# uDuino.net
KiCad netlist of a schematic drawn in EAGLE
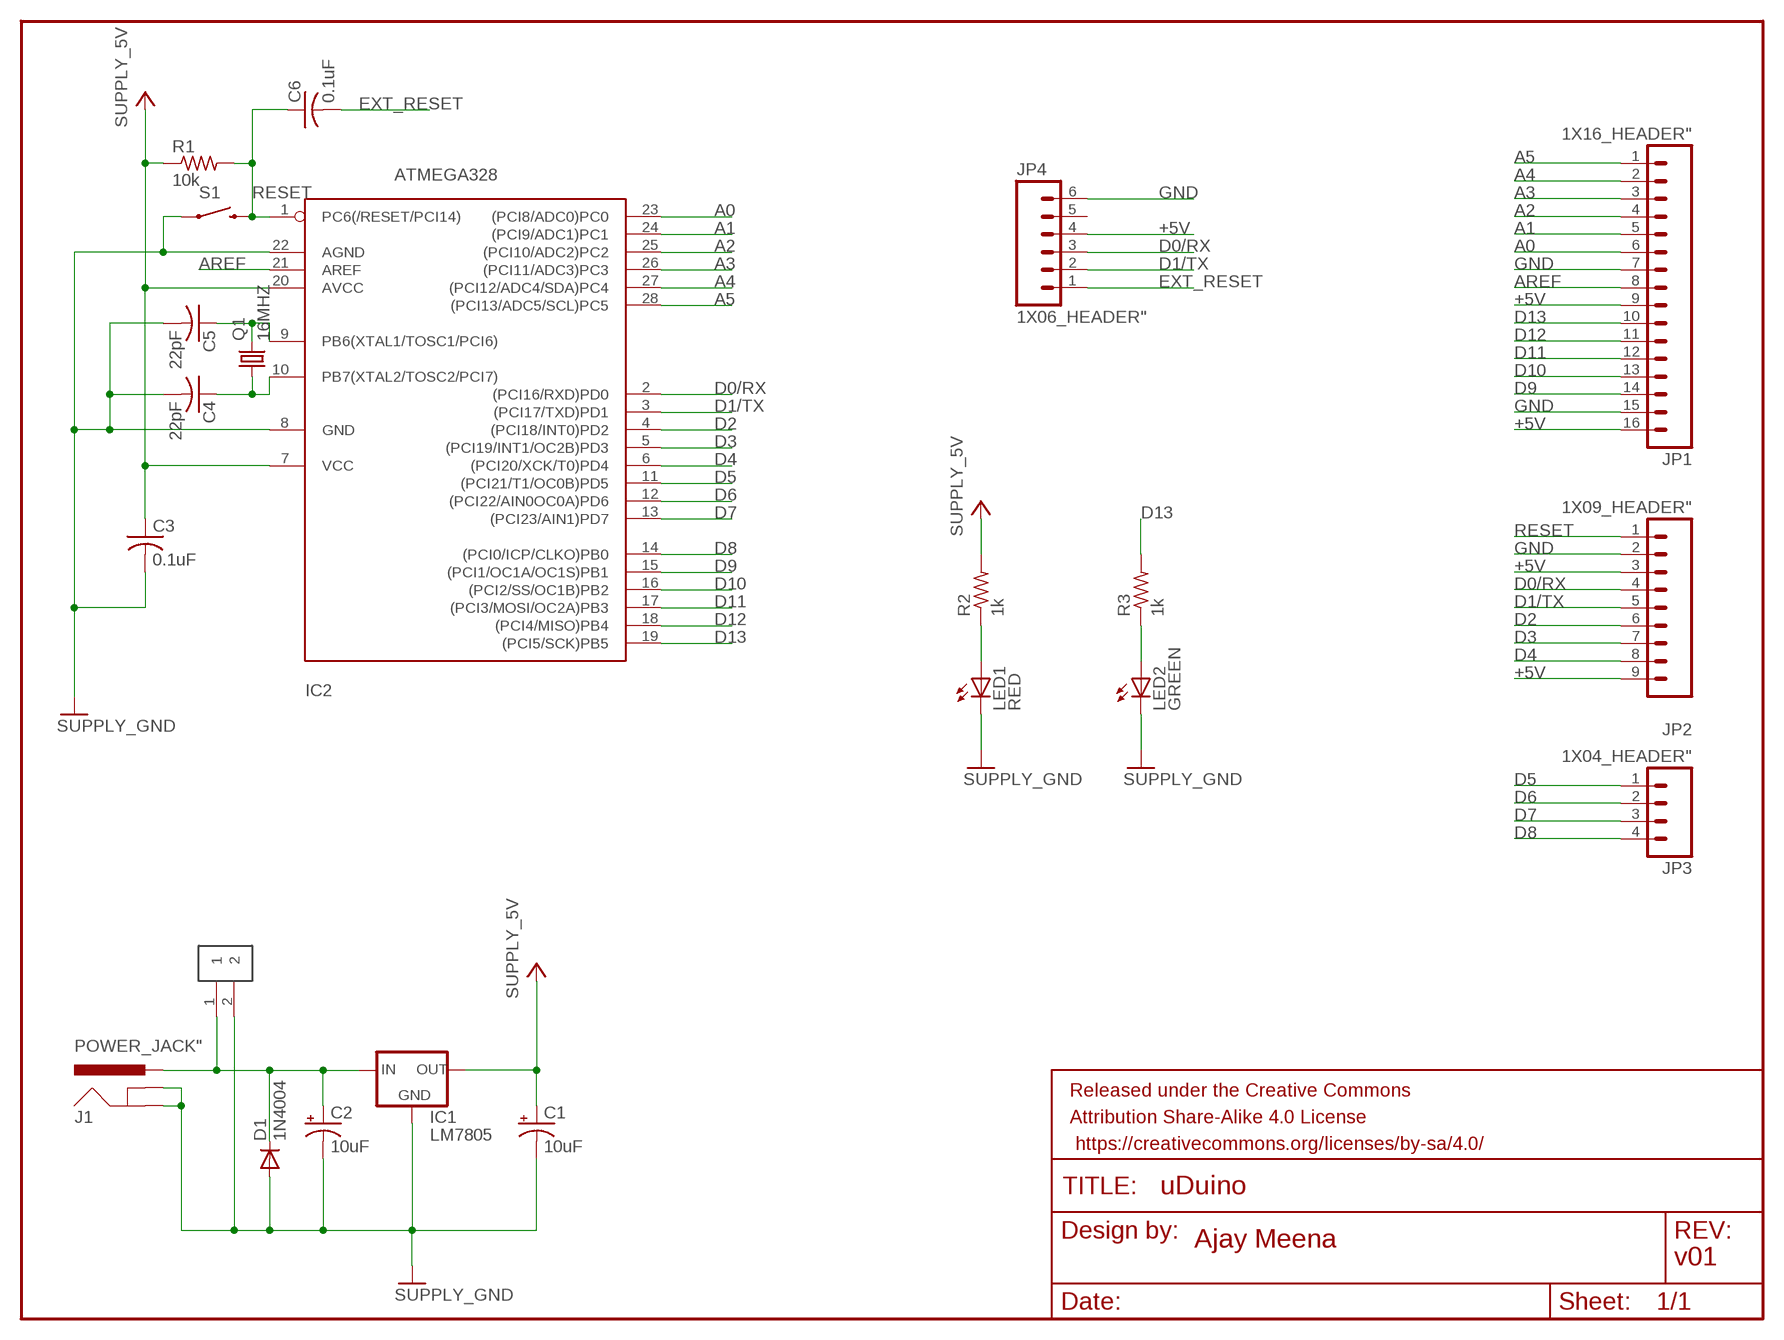
[diagram p0: schematic, sheet 1]

(export (version "E")
  (design (tool "Eeschema 10.0.6"))
  (components
    (comp (ref "C1")
      (value "10uF")
      (footprint "eagle-import:ELECTROLYTIC_CAP")
      (libsource (lib "eagle-import") (part "ELECTROLYTIC_CAP2.54MM"))
    )
    (comp (ref "C2")
      (value "10uF")
      (footprint "eagle-import:ELECTROLYTIC_CAP")
      (libsource (lib "eagle-import") (part "ELECTROLYTIC_CAP2.54MM"))
    )
    (comp (ref "C3")
      (value "0.1uF")
      (footprint "eagle-import:UNPOLARIZED_CAP")
      (libsource (lib "eagle-import") (part "UNPOLARIZED_CAP{dblquote}"))
    )
    (comp (ref "C4")
      (value "22pF")
      (footprint "eagle-import:UNPOLARIZED_CAP")
      (libsource (lib "eagle-import") (part "UNPOLARIZED_CAP{dblquote}"))
    )
    (comp (ref "C5")
      (value "22pF")
      (footprint "eagle-import:UNPOLARIZED_CAP")
      (libsource (lib "eagle-import") (part "UNPOLARIZED_CAP{dblquote}"))
    )
    (comp (ref "C6")
      (value "0.1uF")
      (footprint "eagle-import:UNPOLARIZED_CAP")
      (libsource (lib "eagle-import") (part "UNPOLARIZED_CAP{dblquote}"))
    )
    (comp (ref "D1")
      (value "1N4004")
      (footprint "eagle-import:DO41-10")
      (libsource (lib "eagle-import") (part "1N4004"))
    )
    (comp (ref "FRAME1")
      (value "FRAME-LETTERNO_PACKAGE")
      (footprint "eagle-import:DUMMY")
      (fields
        (field (name "DESIGNER") "Nobody")
        (field (name "VERSION") "v01")
        (field (name "DESIGNER_1") "Ajay Meena")
      )
      (libsource (lib "eagle-import") (part "FRAME-LETTERNO_PACKAGE"))
    )
    (comp (ref "IC1")
      (value "LM7805")
      (footprint "eagle-import:L4931_REGULATOR")
      (libsource (lib "eagle-import") (part "REGULATOR"))
    )
    (comp (ref "IC2")
      (value "ATMEGA328")
      (footprint "eagle-import:ATMEGA328")
      (libsource (lib "eagle-import") (part "ATMEGA328{dblquote}"))
    )
    (comp (ref "J1")
      (value "POWER_JACK\"")
      (footprint "eagle-import:POWER_JACK")
      (libsource (lib "eagle-import") (part "POWER_JACK{dblquote}"))
    )
    (comp (ref "JP1")
      (value "1X16_HEADER\"")
      (footprint "eagle-import:1X16_HEADER")
      (libsource (lib "eagle-import") (part "1X16_HEADER{dblquote}"))
    )
    (comp (ref "JP2")
      (value "1X09_HEADER\"")
      (footprint "eagle-import:1X09_HEADER")
      (libsource (lib "eagle-import") (part "1X09_HEADER{dblquote}"))
    )
    (comp (ref "JP3")
      (value "1X04_HEADER\"")
      (footprint "eagle-import:1X04_HEADER")
      (libsource (lib "eagle-import") (part "1X04_HEADER{dblquote}"))
    )
    (comp (ref "JP4")
      (value "1X06_HEADER\"")
      (footprint "eagle-import:1X06_HEADER")
      (libsource (lib "eagle-import") (part "1X06_HEADER{dblquote}"))
    )
    (comp (ref "LED1")
      (value "RED")
      (footprint "eagle-import:LED5MM")
      (libsource (lib "eagle-import") (part "LED5MM"))
    )
    (comp (ref "LED2")
      (value "GREEN")
      (footprint "eagle-import:LED5MM")
      (libsource (lib "eagle-import") (part "LED5MM"))
    )
    (comp (ref "Q1")
      (value "16MHZ")
      (footprint "eagle-import:HC49_S")
      (libsource (lib "eagle-import") (part "CRYSTALHC49S"))
    )
    (comp (ref "R1")
      (value "10k")
      (footprint "eagle-import:0204_7")
      (libsource (lib "eagle-import") (part "R-US_0204/7"))
    )
    (comp (ref "R2")
      (value "1k")
      (footprint "eagle-import:0204_7")
      (libsource (lib "eagle-import") (part "R-US_0204/7"))
    )
    (comp (ref "R3")
      (value "1k")
      (footprint "eagle-import:0204_7")
      (libsource (lib "eagle-import") (part "R-US_0204/7"))
    )
    (comp (ref "S1")
      (value "MOMENTARY_SWITCH\"")
      (footprint "eagle-import:MOMENTARY_SWITCH")
      (libsource (lib "eagle-import") (part "MOMENTARY_SWITCH{dblquote}"))
    )
    (comp (ref "U$1")
      (value "1X02_HEADER")
      (footprint "eagle-import:1X02_HEADER")
      (libsource (lib "eagle-import") (part "1X02_HEADER"))
    )
  )
  (nets
    (net (code "1") (name "/A0") (class "Default")
      (node (ref "IC2") (pin "23") (pinfunction "(PCI8/ADC0)PC0_23") (pintype "bidirectional"))
      (node (ref "JP1") (pin "6") (pinfunction "6_6") (pintype "passive"))
    )
    (net (code "2") (name "/A1") (class "Default")
      (node (ref "IC2") (pin "24") (pinfunction "(PCI9/ADC1)PC1_24") (pintype "bidirectional"))
      (node (ref "JP1") (pin "5") (pinfunction "5_5") (pintype "passive"))
    )
    (net (code "3") (name "/A2") (class "Default")
      (node (ref "IC2") (pin "25") (pinfunction "(PCI10/ADC2)PC2_25") (pintype "bidirectional"))
      (node (ref "JP1") (pin "4") (pinfunction "4_4") (pintype "passive"))
    )
    (net (code "4") (name "/A3") (class "Default")
      (node (ref "IC2") (pin "26") (pinfunction "(PCI11/ADC3)PC3_26") (pintype "bidirectional"))
      (node (ref "JP1") (pin "3") (pinfunction "3_3") (pintype "passive"))
    )
    (net (code "5") (name "/A4") (class "Default")
      (node (ref "IC2") (pin "27") (pinfunction "(PCI12/ADC4/SDA)PC4_27") (pintype "bidirectional"))
      (node (ref "JP1") (pin "2") (pinfunction "2_2") (pintype "passive"))
    )
    (net (code "6") (name "/A5") (class "Default")
      (node (ref "IC2") (pin "28") (pinfunction "(PCI13/ADC5/SCL)PC5_28") (pintype "bidirectional"))
      (node (ref "JP1") (pin "1") (pinfunction "1_1") (pintype "passive"))
    )
    (net (code "7") (name "/AREF") (class "Default")
      (node (ref "IC2") (pin "21") (pinfunction "AREF_21") (pintype "bidirectional"))
      (node (ref "JP1") (pin "8") (pinfunction "8_8") (pintype "passive"))
    )
    (net (code "8") (name "/D0{slash}RX") (class "Default")
      (node (ref "IC2") (pin "2") (pinfunction "(PCI16/RXD)PD0_2") (pintype "bidirectional"))
      (node (ref "JP2") (pin "4") (pinfunction "4_4") (pintype "passive"))
      (node (ref "JP4") (pin "3") (pinfunction "3_3") (pintype "passive"))
    )
    (net (code "9") (name "/D1{slash}TX") (class "Default")
      (node (ref "IC2") (pin "3") (pinfunction "(PCI17/TXD)PD1_3") (pintype "bidirectional"))
      (node (ref "JP2") (pin "5") (pinfunction "5_5") (pintype "passive"))
      (node (ref "JP4") (pin "2") (pinfunction "2_2") (pintype "passive"))
    )
    (net (code "10") (name "/D2") (class "Default")
      (node (ref "IC2") (pin "4") (pinfunction "(PCI18/INT0)PD2_4") (pintype "bidirectional"))
      (node (ref "JP2") (pin "6") (pinfunction "6_6") (pintype "passive"))
    )
    (net (code "11") (name "/D3") (class "Default")
      (node (ref "IC2") (pin "5") (pinfunction "(PCI19/INT1/OC2B)PD3_5") (pintype "bidirectional"))
      (node (ref "JP2") (pin "7") (pinfunction "7_7") (pintype "passive"))
    )
    (net (code "12") (name "/D4") (class "Default")
      (node (ref "IC2") (pin "6") (pinfunction "(PCI20/XCK/T0)PD4_6") (pintype "bidirectional"))
      (node (ref "JP2") (pin "8") (pinfunction "8_8") (pintype "passive"))
    )
    (net (code "13") (name "/D5") (class "Default")
      (node (ref "IC2") (pin "11") (pinfunction "(PCI21/T1/OC0B)PD5_11") (pintype "bidirectional"))
      (node (ref "JP3") (pin "1") (pinfunction "1_1") (pintype "passive"))
    )
    (net (code "14") (name "/D6") (class "Default")
      (node (ref "IC2") (pin "12") (pinfunction "(PCI22/AIN0OC0A)PD6_12") (pintype "bidirectional"))
      (node (ref "JP3") (pin "2") (pinfunction "2_2") (pintype "passive"))
    )
    (net (code "15") (name "/D7") (class "Default")
      (node (ref "IC2") (pin "13") (pinfunction "(PCI23/AIN1)PD7_13") (pintype "bidirectional"))
      (node (ref "JP3") (pin "3") (pinfunction "3_3") (pintype "passive"))
    )
    (net (code "16") (name "/D8") (class "Default")
      (node (ref "IC2") (pin "14") (pinfunction "(PCI0/ICP/CLKO)PB0_14") (pintype "bidirectional"))
      (node (ref "JP3") (pin "4") (pinfunction "4_4") (pintype "passive"))
    )
    (net (code "17") (name "/D9") (class "Default")
      (node (ref "IC2") (pin "15") (pinfunction "(PCI1/OC1A/OC1S)PB1_15") (pintype "bidirectional"))
      (node (ref "JP1") (pin "14") (pinfunction "14_14") (pintype "passive"))
    )
    (net (code "18") (name "/D10") (class "Default")
      (node (ref "IC2") (pin "16") (pinfunction "(PCI2/SS/OC1B)PB2_16") (pintype "bidirectional"))
      (node (ref "JP1") (pin "13") (pinfunction "13_13") (pintype "passive"))
    )
    (net (code "19") (name "/D11") (class "Default")
      (node (ref "IC2") (pin "17") (pinfunction "(PCI3/MOSI/OC2A)PB3_17") (pintype "bidirectional"))
      (node (ref "JP1") (pin "12") (pinfunction "12_12") (pintype "passive"))
    )
    (net (code "20") (name "/D12") (class "Default")
      (node (ref "IC2") (pin "18") (pinfunction "(PCI4/MISO)PB4_18") (pintype "bidirectional"))
      (node (ref "JP1") (pin "11") (pinfunction "11_11") (pintype "passive"))
    )
    (net (code "21") (name "/D13") (class "Default")
      (node (ref "IC2") (pin "19") (pinfunction "(PCI5/SCK)PB5_19") (pintype "bidirectional"))
      (node (ref "JP1") (pin "10") (pinfunction "10_10") (pintype "passive"))
      (node (ref "R3") (pin "2") (pinfunction "2_2") (pintype "passive"))
    )
    (net (code "22") (name "/EXT_RESET") (class "Default")
      (node (ref "C6") (pin "2") (pinfunction "2_2") (pintype "passive"))
      (node (ref "JP4") (pin "1") (pinfunction "1_1") (pintype "passive"))
    )
    (net (code "23") (name "/RESET") (class "Default")
      (node (ref "C6") (pin "1") (pinfunction "1_1") (pintype "passive"))
      (node (ref "IC2") (pin "1") (pinfunction "PC6(/RESET/PCI14)_1") (pintype "bidirectional"))
      (node (ref "JP2") (pin "1") (pinfunction "1_1") (pintype "passive"))
      (node (ref "R1") (pin "2") (pinfunction "2_2") (pintype "passive"))
      (node (ref "S1") (pin "3") (pinfunction "2_3") (pintype "passive"))
    )
    (net (code "24") (name "Net-(C2-Pad+)") (class "Default")
      (node (ref "C2") (pin "+") (pinfunction "+_+") (pintype "passive"))
      (node (ref "D1") (pin "C") (pinfunction "C_C") (pintype "passive"))
      (node (ref "IC1") (pin "IN") (pinfunction "IN_IN") (pintype "input"))
      (node (ref "J1") (pin "PWR") (pinfunction "PWR_PWR") (pintype "bidirectional"))
      (node (ref "U$1") (pin "1") (pinfunction "1_1") (pintype "bidirectional"))
    )
    (net (code "25") (name "Net-(IC2-PB6(XTAL1{slash}TOSC1{slash}PCI6))") (class "Default")
      (node (ref "C5") (pin "1") (pinfunction "1_1") (pintype "passive"))
      (node (ref "IC2") (pin "9") (pinfunction "PB6(XTAL1/TOSC1/PCI6)_9") (pintype "bidirectional"))
      (node (ref "Q1") (pin "2") (pinfunction "2_2") (pintype "passive"))
    )
    (net (code "26") (name "Net-(IC2-PB7(XTAL2{slash}TOSC2{slash}PCI7))") (class "Default")
      (node (ref "C4") (pin "1") (pinfunction "1_1") (pintype "passive"))
      (node (ref "IC2") (pin "10") (pinfunction "PB7(XTAL2/TOSC2/PCI7)_10") (pintype "bidirectional"))
      (node (ref "Q1") (pin "1") (pinfunction "1_1") (pintype "passive"))
    )
    (net (code "27") (name "Net-(LED1-PadA)") (class "Default")
      (node (ref "LED1") (pin "A") (pinfunction "A_A") (pintype "passive"))
      (node (ref "R2") (pin "1") (pinfunction "1_1") (pintype "passive"))
    )
    (net (code "28") (name "Net-(LED2-PadA)") (class "Default")
      (node (ref "LED2") (pin "A") (pinfunction "A_A") (pintype "passive"))
      (node (ref "R3") (pin "1") (pinfunction "1_1") (pintype "passive"))
    )
    (net (code "29") (name "SUPPLY_5V") (class "Default")
      (node (ref "C1") (pin "+") (pinfunction "+_+") (pintype "passive"))
      (node (ref "C3") (pin "1") (pinfunction "1_1") (pintype "passive"))
      (node (ref "IC1") (pin "OUT") (pinfunction "OUT_OUT") (pintype "passive"))
      (node (ref "IC2") (pin "20") (pinfunction "AVCC_20") (pintype "bidirectional"))
      (node (ref "IC2") (pin "7") (pinfunction "VCC_7") (pintype "bidirectional"))
      (node (ref "JP1") (pin "16") (pinfunction "16_16") (pintype "passive"))
      (node (ref "JP1") (pin "9") (pinfunction "9_9") (pintype "passive"))
      (node (ref "JP2") (pin "3") (pinfunction "3_3") (pintype "passive"))
      (node (ref "JP2") (pin "9") (pinfunction "9_9") (pintype "passive"))
      (node (ref "JP4") (pin "4") (pinfunction "4_4") (pintype "passive"))
      (node (ref "R1") (pin "1") (pinfunction "1_1") (pintype "passive"))
      (node (ref "R2") (pin "2") (pinfunction "2_2") (pintype "passive"))
    )
    (net (code "30") (name "SUPPLY_GND") (class "Default")
      (node (ref "C1") (pin "-") (pinfunction "-_-") (pintype "passive"))
      (node (ref "C2") (pin "-") (pinfunction "-_-") (pintype "passive"))
      (node (ref "C3") (pin "2") (pinfunction "2_2") (pintype "passive"))
      (node (ref "C4") (pin "2") (pinfunction "2_2") (pintype "passive"))
      (node (ref "C5") (pin "2") (pinfunction "2_2") (pintype "passive"))
      (node (ref "D1") (pin "A") (pinfunction "A_A") (pintype "passive"))
      (node (ref "IC1") (pin "GND") (pinfunction "GND_GND") (pintype "input"))
      (node (ref "IC2") (pin "22") (pinfunction "AGND_22") (pintype "bidirectional"))
      (node (ref "IC2") (pin "8") (pinfunction "GND_8") (pintype "bidirectional"))
      (node (ref "J1") (pin "GND") (pinfunction "GND_GND") (pintype "bidirectional"))
      (node (ref "J1") (pin "GNDBREAK") (pinfunction "GNDBREAK_GNDBREAK") (pintype "bidirectional"))
      (node (ref "JP1") (pin "15") (pinfunction "15_15") (pintype "passive"))
      (node (ref "JP1") (pin "7") (pinfunction "7_7") (pintype "passive"))
      (node (ref "JP2") (pin "2") (pinfunction "2_2") (pintype "passive"))
      (node (ref "JP4") (pin "6") (pinfunction "6_6") (pintype "passive"))
      (node (ref "LED1") (pin "K") (pinfunction "C_K") (pintype "passive"))
      (node (ref "LED2") (pin "K") (pinfunction "C_K") (pintype "passive"))
      (node (ref "S1") (pin "1") (pinfunction "1_1") (pintype "passive"))
      (node (ref "U$1") (pin "2") (pinfunction "2_2") (pintype "bidirectional"))
    )
    (net (code "31") (name "unconnected-(JP4-Pad5)") (class "Default")
      (node (ref "JP4") (pin "5") (pinfunction "5_5") (pintype "passive"))
    )
  )
)
